# 2.net
KiCad netlist of a schematic drawn in Altium Designer
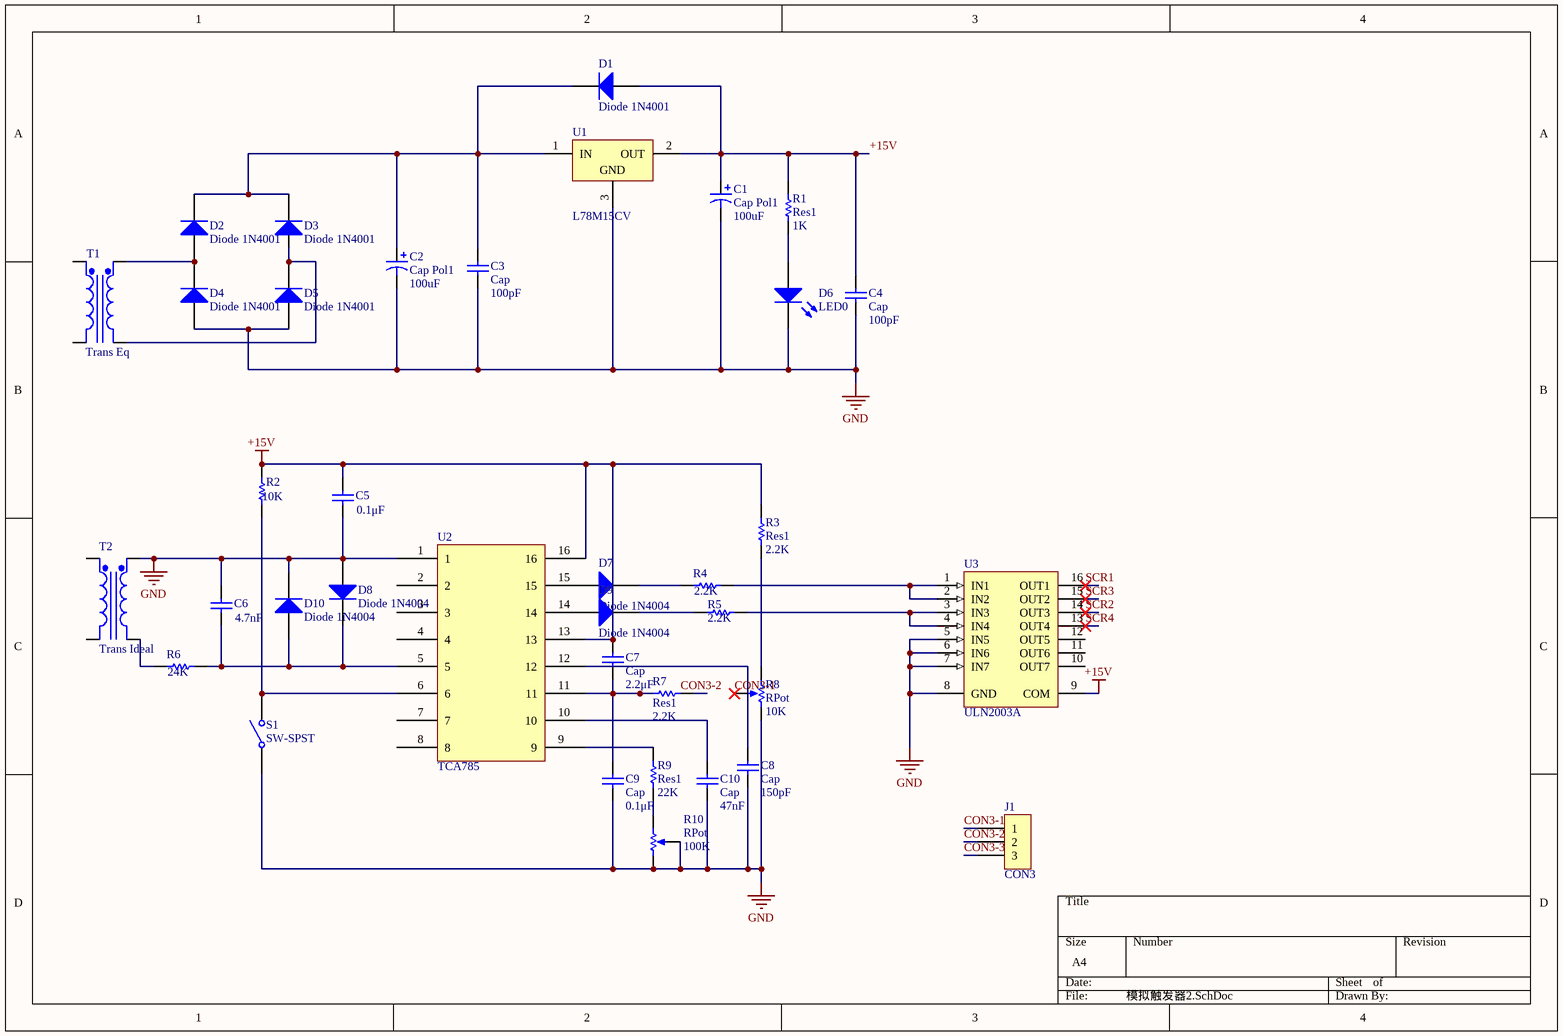
[diagram p0: 模拟触发器2.SchDoc]

(export (version "E")
  (design (tool "Eeschema 10.0.6"))
  (components
    (comp (ref "C1")
      (value "Cap Pol1")
      (footprint "RB7.6-15")
      (description "Polarized Capacitor (Radial)")
      (fields (field (name "ALTIUM_VALUE") "100uF") (field (name "PUBLISHER") "Altium Limited"))
      (libsource (lib "Miscellaneous Devices") (part "Cap Pol1"))
    )
    (comp (ref "C2")
      (value "Cap Pol1")
      (footprint "RB7.6-15")
      (description "Polarized Capacitor (Radial)")
      (fields (field (name "ALTIUM_VALUE") "100uF") (field (name "PUBLISHER") "Altium Limited"))
      (libsource (lib "Miscellaneous Devices") (part "Cap Pol1"))
    )
    (comp (ref "C3")
      (value "Cap")
      (footprint "6-0805")
      (description "Capacitor")
      (fields (field (name "ALTIUM_VALUE") "100pF") (field (name "PUBLISHER") "Altium Limited"))
      (libsource (lib "Miscellaneous Devices") (part "Cap"))
    )
    (comp (ref "C4")
      (value "Cap")
      (footprint "6-0805")
      (description "Capacitor")
      (fields (field (name "ALTIUM_VALUE") "100pF") (field (name "PUBLISHER") "Altium Limited"))
      (libsource (lib "Miscellaneous Devices") (part "Cap"))
    )
    (comp (ref "C5")
      (value "0.1μF")
      (footprint "6-0805")
      (description "Capacitor")
      (fields (field (name "Comment") "Cap") (field (name "PUBLISHER") "Altium Limited"))
      (libsource (lib "Miscellaneous Devices") (part "Cap"))
    )
    (comp (ref "C6")
      (value "4.7nF")
      (footprint "6-0805")
      (description "Capacitor")
      (fields (field (name "Comment") "Cap") (field (name "PUBLISHER") "Altium Limited"))
      (libsource (lib "Miscellaneous Devices") (part "Cap"))
    )
    (comp (ref "C7")
      (value "Cap")
      (footprint "6-0805")
      (description "Capacitor")
      (fields (field (name "ALTIUM_VALUE") "2.2μF") (field (name "PUBLISHER") "Altium Limited"))
      (libsource (lib "Miscellaneous Devices") (part "Cap"))
    )
    (comp (ref "C8")
      (value "Cap")
      (footprint "6-0805")
      (description "Capacitor")
      (fields (field (name "ALTIUM_VALUE") "150pF") (field (name "PUBLISHER") "Altium Limited"))
      (libsource (lib "Miscellaneous Devices") (part "Cap"))
    )
    (comp (ref "C9")
      (value "Cap")
      (footprint "6-0805")
      (description "Capacitor")
      (fields (field (name "ALTIUM_VALUE") "0.1μF") (field (name "PUBLISHER") "Altium Limited"))
      (libsource (lib "Miscellaneous Devices") (part "Cap"))
    )
    (comp (ref "C10")
      (value "Cap")
      (footprint "6-0805")
      (description "Capacitor")
      (fields (field (name "ALTIUM_VALUE") "47nF") (field (name "PUBLISHER") "Altium Limited"))
      (libsource (lib "Miscellaneous Devices") (part "Cap"))
    )
    (comp (ref "D1")
      (value "Diode 1N4001")
      (footprint "DO-41")
      (description "1 Amp General Purpose Rectifier")
      (fields (field (name "PUBLISHER") "Altium Limited"))
      (libsource (lib "Miscellaneous Devices") (part "Diode 1N4001"))
    )
    (comp (ref "D2")
      (value "Diode 1N4001")
      (footprint "DO-41")
      (description "1 Amp General Purpose Rectifier")
      (fields (field (name "PUBLISHER") "Altium Limited"))
      (libsource (lib "Miscellaneous Devices") (part "Diode 1N4001"))
    )
    (comp (ref "D3")
      (value "Diode 1N4001")
      (footprint "DO-41")
      (description "1 Amp General Purpose Rectifier")
      (fields (field (name "PUBLISHER") "Altium Limited"))
      (libsource (lib "Miscellaneous Devices") (part "Diode 1N4001"))
    )
    (comp (ref "D4")
      (value "Diode 1N4001")
      (footprint "DO-41")
      (description "1 Amp General Purpose Rectifier")
      (fields (field (name "PUBLISHER") "Altium Limited"))
      (libsource (lib "Miscellaneous Devices") (part "Diode 1N4001"))
    )
    (comp (ref "D5")
      (value "Diode 1N4001")
      (footprint "DO-41")
      (description "1 Amp General Purpose Rectifier")
      (fields (field (name "PUBLISHER") "Altium Limited"))
      (libsource (lib "Miscellaneous Devices") (part "Diode 1N4001"))
    )
    (comp (ref "D6")
      (value "LED0")
      (footprint "6-0805")
      (description "Typical INFRARED GaAs LED")
      (fields (field (name "PUBLISHER") "Altium Limited"))
      (libsource (lib "Miscellaneous Devices") (part "LED0"))
    )
    (comp (ref "D7")
      (value "Diode 1N4004")
      (footprint "DO-41")
      (description "1 Amp General Purpose Rectifier")
      (fields (field (name "PUBLISHER") "Altium Limited"))
      (libsource (lib "Miscellaneous Devices") (part "Diode 1N4004"))
    )
    (comp (ref "D8")
      (value "Diode 1N4004")
      (footprint "DO-41")
      (description "1 Amp General Purpose Rectifier")
      (fields (field (name "PUBLISHER") "Altium Limited"))
      (libsource (lib "Miscellaneous Devices") (part "Diode 1N4004"))
    )
    (comp (ref "D9")
      (value "Diode 1N4004")
      (footprint "DO-41")
      (description "1 Amp General Purpose Rectifier")
      (fields (field (name "PUBLISHER") "Altium Limited"))
      (libsource (lib "Miscellaneous Devices") (part "Diode 1N4004"))
    )
    (comp (ref "D10")
      (value "Diode 1N4004")
      (footprint "DO-41")
      (description "1 Amp General Purpose Rectifier")
      (fields (field (name "PUBLISHER") "Altium Limited"))
      (libsource (lib "Miscellaneous Devices") (part "Diode 1N4004"))
    )
    (comp (ref "J1") (value "CON3") (footprint "DG1283-5.0") (libsource (lib "常用元件库") (part "CON3")))
    (comp (ref "R1")
      (value "Res1")
      (footprint "6-0805")
      (description "Resistor")
      (fields (field (name "ALTIUM_VALUE") "1K") (field (name "PUBLISHER") "Altium Limited"))
      (libsource (lib "Miscellaneous Devices") (part "Res1"))
    )
    (comp (ref "R2")
      (value "10K")
      (footprint "6-0805")
      (description "Resistor")
      (fields (field (name "Comment") "Res1") (field (name "PUBLISHER") "Altium Limited"))
      (libsource (lib "Miscellaneous Devices") (part "Res1"))
    )
    (comp (ref "R3")
      (value "Res1")
      (footprint "6-0805")
      (description "Resistor")
      (fields (field (name "ALTIUM_VALUE") "2.2K") (field (name "PUBLISHER") "Altium Limited"))
      (libsource (lib "Miscellaneous Devices") (part "Res1"))
    )
    (comp (ref "R4")
      (value "2.2K")
      (footprint "6-0805")
      (description "Resistor")
      (fields (field (name "Comment") "Res1") (field (name "PUBLISHER") "Altium Limited"))
      (libsource (lib "Miscellaneous Devices") (part "Res1"))
    )
    (comp (ref "R5")
      (value "2.2K")
      (footprint "6-0805")
      (description "Resistor")
      (fields (field (name "Comment") "Res1") (field (name "PUBLISHER") "Altium Limited"))
      (libsource (lib "Miscellaneous Devices") (part "Res1"))
    )
    (comp (ref "R6")
      (value "24K")
      (footprint "1206")
      (description "Resistor")
      (fields (field (name "Comment") "Res1") (field (name "PUBLISHER") "Altium Limited"))
      (libsource (lib "Miscellaneous Devices") (part "Res1"))
    )
    (comp (ref "R7")
      (value "Res1")
      (footprint "6-0805")
      (description "Resistor")
      (fields (field (name "ALTIUM_VALUE") "2.2K") (field (name "PUBLISHER") "Altium Limited"))
      (libsource (lib "Miscellaneous Devices") (part "Res1"))
    )
    (comp (ref "R8")
      (value "RPot")
      (footprint "VR5")
      (description "Potentiometer")
      (fields (field (name "ALTIUM_VALUE") "10K") (field (name "PUBLISHER") "Altium Limited"))
      (libsource (lib "Miscellaneous Devices") (part "RPot"))
    )
    (comp (ref "R9")
      (value "Res1")
      (footprint "6-0805")
      (description "Resistor")
      (fields (field (name "ALTIUM_VALUE") "22K") (field (name "PUBLISHER") "Altium Limited"))
      (libsource (lib "Miscellaneous Devices") (part "Res1"))
    )
    (comp (ref "R10")
      (value "RPot")
      (footprint "VR5")
      (description "Potentiometer")
      (fields (field (name "ALTIUM_VALUE") "100K") (field (name "PUBLISHER") "Altium Limited"))
      (libsource (lib "Miscellaneous Devices") (part "RPot"))
    )
    (comp (ref "S1")
      (value "SW-SPST")
      (footprint "SPST-2")
      (description "Single-Pole, Single-Throw Switch")
      (fields (field (name "PUBLISHER") "Altium Limited"))
      (libsource (lib "Miscellaneous Devices") (part "SW-SPST"))
    )
    (comp (ref "T1")
      (value "Trans Eq")
      (footprint "TRF_4")
      (description "Transformer (Equivalent Circuit Model)")
      (fields (field (name "PUBLISHER") "Altium Limited"))
      (libsource (lib "Miscellaneous Devices") (part "Trans Eq"))
    )
    (comp (ref "T2")
      (value "Trans Ideal")
      (footprint "TRF_4")
      (description "Transformer (Ideal)")
      (fields (field (name "PUBLISHER") "Altium Limited"))
      (libsource (lib "Miscellaneous Devices") (part "Trans Ideal"))
    )
    (comp (ref "U1")
      (value "L78M15CV")
      (footprint "TO220V")
      (description "Positive Voltage Regulator")
      (fields (field (name "PUBLISHER") "Altium Limited"))
      (libsource (lib "ST Power Mgt Voltage Regulator") (part "L78M15CV"))
    )
    (comp (ref "U2")
      (value "TCA785")
      (footprint "Miscellaneous Devices:DIP-16")
      (libsource (lib "TCA785") (part "TCA785"))
    )
    (comp (ref "U3")
      (value "ULN2003A")
      (footprint "A16")
      (description "High-Voltage, High-Current Darlington Array")
      (fields (field (name "PUBLISHER") "Altium Limited"))
      (libsource (lib "Allegro Interface Darlington Driver") (part "ULN2003A"))
    )
  )
  (nets
    (net (code "1") (name "+15V") (class "Default")
      (node (ref "C1") (pin "1") (pinfunction "1_1") (pintype "passive"))
      (node (ref "C4") (pin "2") (pinfunction "2_2") (pintype "passive"))
      (node (ref "C5") (pin "2") (pinfunction "2_2") (pintype "passive"))
      (node (ref "C7") (pin "2") (pinfunction "2_2") (pintype "passive"))
      (node (ref "D1") (pin "1") (pinfunction "A_1") (pintype "passive"))
      (node (ref "R1") (pin "2") (pinfunction "2_2") (pintype "passive"))
      (node (ref "R2") (pin "2") (pinfunction "2_2") (pintype "passive"))
      (node (ref "R3") (pin "2") (pinfunction "2_2") (pintype "passive"))
      (node (ref "U1") (pin "2") (pinfunction "OUT_2") (pintype "power_in"))
      (node (ref "U2") (pin "13") (pinfunction "13_13") (pintype "passive"))
      (node (ref "U2") (pin "16") (pinfunction "16_16") (pintype "passive"))
      (node (ref "U3") (pin "9") (pinfunction "COM_9") (pintype "passive"))
    )
    (net (code "2") (name "/CON3-1") (class "Default")
      (node (ref "J1") (pin "1") (pinfunction "1_1") (pintype "passive"))
      (node (ref "R8") (pin "3") (pinfunction "TAP_3") (pintype "passive"))
    )
    (net (code "3") (name "/CON3-2") (class "Default")
      (node (ref "J1") (pin "2") (pinfunction "2_2") (pintype "passive"))
    )
    (net (code "4") (name "/CON3-3") (class "Default")
      (node (ref "J1") (pin "3") (pinfunction "3_3") (pintype "passive"))
    )
    (net (code "5") (name "/SCR1") (class "Default")
      (node (ref "U3") (pin "16") (pinfunction "OUT1_16") (pintype "open_collector+no_connect"))
    )
    (net (code "6") (name "/SCR2") (class "Default")
      (node (ref "U3") (pin "14") (pinfunction "OUT3_14") (pintype "open_collector+no_connect"))
    )
    (net (code "7") (name "/SCR3") (class "Default")
      (node (ref "U3") (pin "15") (pinfunction "OUT2_15") (pintype "open_collector+no_connect"))
    )
    (net (code "8") (name "/SCR4") (class "Default")
      (node (ref "U3") (pin "13") (pinfunction "OUT4_13") (pintype "open_collector+no_connect"))
    )
    (net (code "9") (name "GND") (class "Default")
      (node (ref "C1") (pin "2") (pinfunction "2_2") (pintype "passive"))
      (node (ref "C10") (pin "1") (pinfunction "1_1") (pintype "passive"))
      (node (ref "C2") (pin "2") (pinfunction "2_2") (pintype "passive"))
      (node (ref "C3") (pin "1") (pinfunction "1_1") (pintype "passive"))
      (node (ref "C4") (pin "1") (pinfunction "1_1") (pintype "passive"))
      (node (ref "C5") (pin "1") (pinfunction "1_1") (pintype "passive"))
      (node (ref "C6") (pin "2") (pinfunction "2_2") (pintype "passive"))
      (node (ref "C8") (pin "1") (pinfunction "1_1") (pintype "passive"))
      (node (ref "C9") (pin "1") (pinfunction "1_1") (pintype "passive"))
      (node (ref "D10") (pin "2") (pinfunction "K_2") (pintype "passive"))
      (node (ref "D4") (pin "1") (pinfunction "A_1") (pintype "passive"))
      (node (ref "D5") (pin "1") (pinfunction "A_1") (pintype "passive"))
      (node (ref "D6") (pin "2") (pinfunction "K_2") (pintype "passive"))
      (node (ref "D8") (pin "1") (pinfunction "A_1") (pintype "passive"))
      (node (ref "R10") (pin "1") (pinfunction "TOP_1") (pintype "passive"))
      (node (ref "R10") (pin "3") (pinfunction "TAP_3") (pintype "passive"))
      (node (ref "R8") (pin "2") (pinfunction "BOT_2") (pintype "passive"))
      (node (ref "S1") (pin "1") (pinfunction "COMMON_1") (pintype "passive"))
      (node (ref "T2") (pin "3") (pinfunction "Sec+_3") (pintype "passive"))
      (node (ref "U1") (pin "3") (pinfunction "GND_3") (pintype "power_in"))
      (node (ref "U2") (pin "1") (pinfunction "1_1") (pintype "passive"))
      (node (ref "U3") (pin "5") (pinfunction "IN5_5") (pintype "input"))
      (node (ref "U3") (pin "6") (pinfunction "IN6_6") (pintype "input"))
      (node (ref "U3") (pin "7") (pinfunction "IN7_7") (pintype "input"))
      (node (ref "U3") (pin "8") (pinfunction "GND_8") (pintype "power_in"))
    )
    (net (code "10") (name "Net-(C7-Pad1)") (class "Default")
      (node (ref "C7") (pin "1") (pinfunction "1_1") (pintype "passive"))
      (node (ref "C9") (pin "2") (pinfunction "2_2") (pintype "passive"))
      (node (ref "R7") (pin "2") (pinfunction "2_2") (pintype "passive"))
      (node (ref "U2") (pin "11") (pinfunction "11_11") (pintype "passive"))
    )
    (net (code "11") (name "Net-(C8-Pad2)") (class "Default")
      (node (ref "C8") (pin "2") (pinfunction "2_2") (pintype "passive"))
      (node (ref "U2") (pin "12") (pinfunction "12_12") (pintype "passive"))
    )
    (net (code "12") (name "Net-(C10-Pad2)") (class "Default")
      (node (ref "C10") (pin "2") (pinfunction "2_2") (pintype "passive"))
      (node (ref "U2") (pin "10") (pinfunction "10_10") (pintype "passive"))
    )
    (net (code "13") (name "Net-(D1-K)") (class "Default")
      (node (ref "C2") (pin "1") (pinfunction "1_1") (pintype "passive"))
      (node (ref "C3") (pin "2") (pinfunction "2_2") (pintype "passive"))
      (node (ref "D1") (pin "2") (pinfunction "K_2") (pintype "passive"))
      (node (ref "D2") (pin "2") (pinfunction "K_2") (pintype "passive"))
      (node (ref "D3") (pin "2") (pinfunction "K_2") (pintype "passive"))
      (node (ref "U1") (pin "1") (pinfunction "IN_1") (pintype "power_in"))
    )
    (net (code "14") (name "Net-(D2-A)") (class "Default")
      (node (ref "D2") (pin "1") (pinfunction "A_1") (pintype "passive"))
      (node (ref "D4") (pin "2") (pinfunction "K_2") (pintype "passive"))
      (node (ref "T1") (pin "3") (pinfunction "Sec+_3") (pintype "passive"))
    )
    (net (code "15") (name "Net-(D3-A)") (class "Default")
      (node (ref "D3") (pin "1") (pinfunction "A_1") (pintype "passive"))
      (node (ref "D5") (pin "2") (pinfunction "K_2") (pintype "passive"))
      (node (ref "T1") (pin "4") (pinfunction "Sec-_4") (pintype "passive"))
    )
    (net (code "16") (name "Net-(D6-A)") (class "Default")
      (node (ref "D6") (pin "1") (pinfunction "A_1") (pintype "passive"))
      (node (ref "R1") (pin "1") (pinfunction "1_1") (pintype "passive"))
    )
    (net (code "17") (name "Net-(D7-K)") (class "Default")
      (node (ref "D7") (pin "2") (pinfunction "K_2") (pintype "passive"))
      (node (ref "R4") (pin "2") (pinfunction "2_2") (pintype "passive"))
    )
    (net (code "18") (name "Net-(D9-K)") (class "Default")
      (node (ref "D9") (pin "2") (pinfunction "K_2") (pintype "passive"))
      (node (ref "R5") (pin "2") (pinfunction "2_2") (pintype "passive"))
    )
    (net (code "19") (name "Net-(D10-A)") (class "Default")
      (node (ref "C6") (pin "1") (pinfunction "1_1") (pintype "passive"))
      (node (ref "D10") (pin "1") (pinfunction "A_1") (pintype "passive"))
      (node (ref "D8") (pin "2") (pinfunction "K_2") (pintype "passive"))
      (node (ref "R6") (pin "1") (pinfunction "1_1") (pintype "passive"))
      (node (ref "U2") (pin "5") (pinfunction "5_5") (pintype "passive"))
    )
    (net (code "20") (name "Net-(R8-TOP)") (class "Default")
      (node (ref "R3") (pin "1") (pinfunction "1_1") (pintype "passive"))
      (node (ref "R8") (pin "1") (pinfunction "TOP_1") (pintype "passive"))
    )
    (net (code "21") (name "Net-(R9-Pad2)") (class "Default")
      (node (ref "R9") (pin "2") (pinfunction "2_2") (pintype "passive"))
      (node (ref "U2") (pin "9") (pinfunction "9_9") (pintype "passive"))
    )
    (net (code "22") (name "Net-(R10-BOT)") (class "Default")
      (node (ref "R10") (pin "2") (pinfunction "BOT_2") (pintype "passive"))
      (node (ref "R9") (pin "1") (pinfunction "1_1") (pintype "passive"))
    )
    (net (code "23") (name "Net-(S1-NO)") (class "Default")
      (node (ref "R2") (pin "1") (pinfunction "1_1") (pintype "passive"))
      (node (ref "S1") (pin "2") (pinfunction "NO_2") (pintype "passive"))
      (node (ref "U2") (pin "6") (pinfunction "6_6") (pintype "passive"))
    )
    (net (code "24") (name "Net-(T2-Sec-)") (class "Default")
      (node (ref "R6") (pin "2") (pinfunction "2_2") (pintype "passive"))
      (node (ref "T2") (pin "4") (pinfunction "Sec-_4") (pintype "passive"))
    )
    (net (code "25") (name "Net-(U3-IN1)") (class "Default")
      (node (ref "R4") (pin "1") (pinfunction "1_1") (pintype "passive"))
      (node (ref "U3") (pin "1") (pinfunction "IN1_1") (pintype "input"))
      (node (ref "U3") (pin "2") (pinfunction "IN2_2") (pintype "input"))
    )
    (net (code "26") (name "Net-(U3-IN3)") (class "Default")
      (node (ref "R5") (pin "1") (pinfunction "1_1") (pintype "passive"))
      (node (ref "U3") (pin "3") (pinfunction "IN3_3") (pintype "input"))
      (node (ref "U3") (pin "4") (pinfunction "IN4_4") (pintype "input"))
    )
    (net (code "27") (name "unconnected-(D7-A-Pad1)") (class "Default")
      (node (ref "D7") (pin "1") (pinfunction "A_1") (pintype "passive"))
    )
    (net (code "28") (name "unconnected-(D9-A-Pad1)") (class "Default")
      (node (ref "D9") (pin "1") (pinfunction "A_1") (pintype "passive"))
    )
    (net (code "29") (name "unconnected-(R7-Pad1)") (class "Default")
      (node (ref "R7") (pin "1") (pinfunction "1_1") (pintype "passive"))
    )
    (net (code "30") (name "unconnected-(T1-Pri+-Pad1)") (class "Default")
      (node (ref "T1") (pin "1") (pinfunction "Pri+_1") (pintype "passive"))
    )
    (net (code "31") (name "unconnected-(T1-Pri--Pad2)") (class "Default")
      (node (ref "T1") (pin "2") (pinfunction "Pri-_2") (pintype "passive"))
    )
    (net (code "32") (name "unconnected-(T2-Pri+-Pad1)") (class "Default")
      (node (ref "T2") (pin "1") (pinfunction "Pri+_1") (pintype "passive"))
    )
    (net (code "33") (name "unconnected-(T2-Pri--Pad2)") (class "Default")
      (node (ref "T2") (pin "2") (pinfunction "Pri-_2") (pintype "passive"))
    )
    (net (code "34") (name "unconnected-(U2-Pad2)") (class "Default")
      (node (ref "U2") (pin "2") (pinfunction "2_2") (pintype "passive"))
    )
    (net (code "35") (name "unconnected-(U2-Pad3)") (class "Default")
      (node (ref "U2") (pin "3") (pinfunction "3_3") (pintype "passive"))
    )
    (net (code "36") (name "unconnected-(U2-Pad4)") (class "Default")
      (node (ref "U2") (pin "4") (pinfunction "4_4") (pintype "passive"))
    )
    (net (code "37") (name "unconnected-(U2-Pad7)") (class "Default")
      (node (ref "U2") (pin "7") (pinfunction "7_7") (pintype "passive"))
    )
    (net (code "38") (name "unconnected-(U2-Pad8)") (class "Default")
      (node (ref "U2") (pin "8") (pinfunction "8_8") (pintype "passive"))
    )
    (net (code "39") (name "unconnected-(U2-Pad14)") (class "Default")
      (node (ref "U2") (pin "14") (pinfunction "14_14") (pintype "passive"))
    )
    (net (code "40") (name "unconnected-(U2-Pad15)") (class "Default")
      (node (ref "U2") (pin "15") (pinfunction "15_15") (pintype "passive"))
    )
    (net (code "41") (name "unconnected-(U3-OUT5-Pad12)") (class "Default")
      (node (ref "U3") (pin "12") (pinfunction "OUT5_12") (pintype "open_collector"))
    )
    (net (code "42") (name "unconnected-(U3-OUT6-Pad11)") (class "Default")
      (node (ref "U3") (pin "11") (pinfunction "OUT6_11") (pintype "open_collector"))
    )
    (net (code "43") (name "unconnected-(U3-OUT7-Pad10)") (class "Default")
      (node (ref "U3") (pin "10") (pinfunction "OUT7_10") (pintype "open_collector"))
    )
  )
)
